# 28Pins_Schematic.net
KiCad netlist of a schematic drawn in Altium Designer
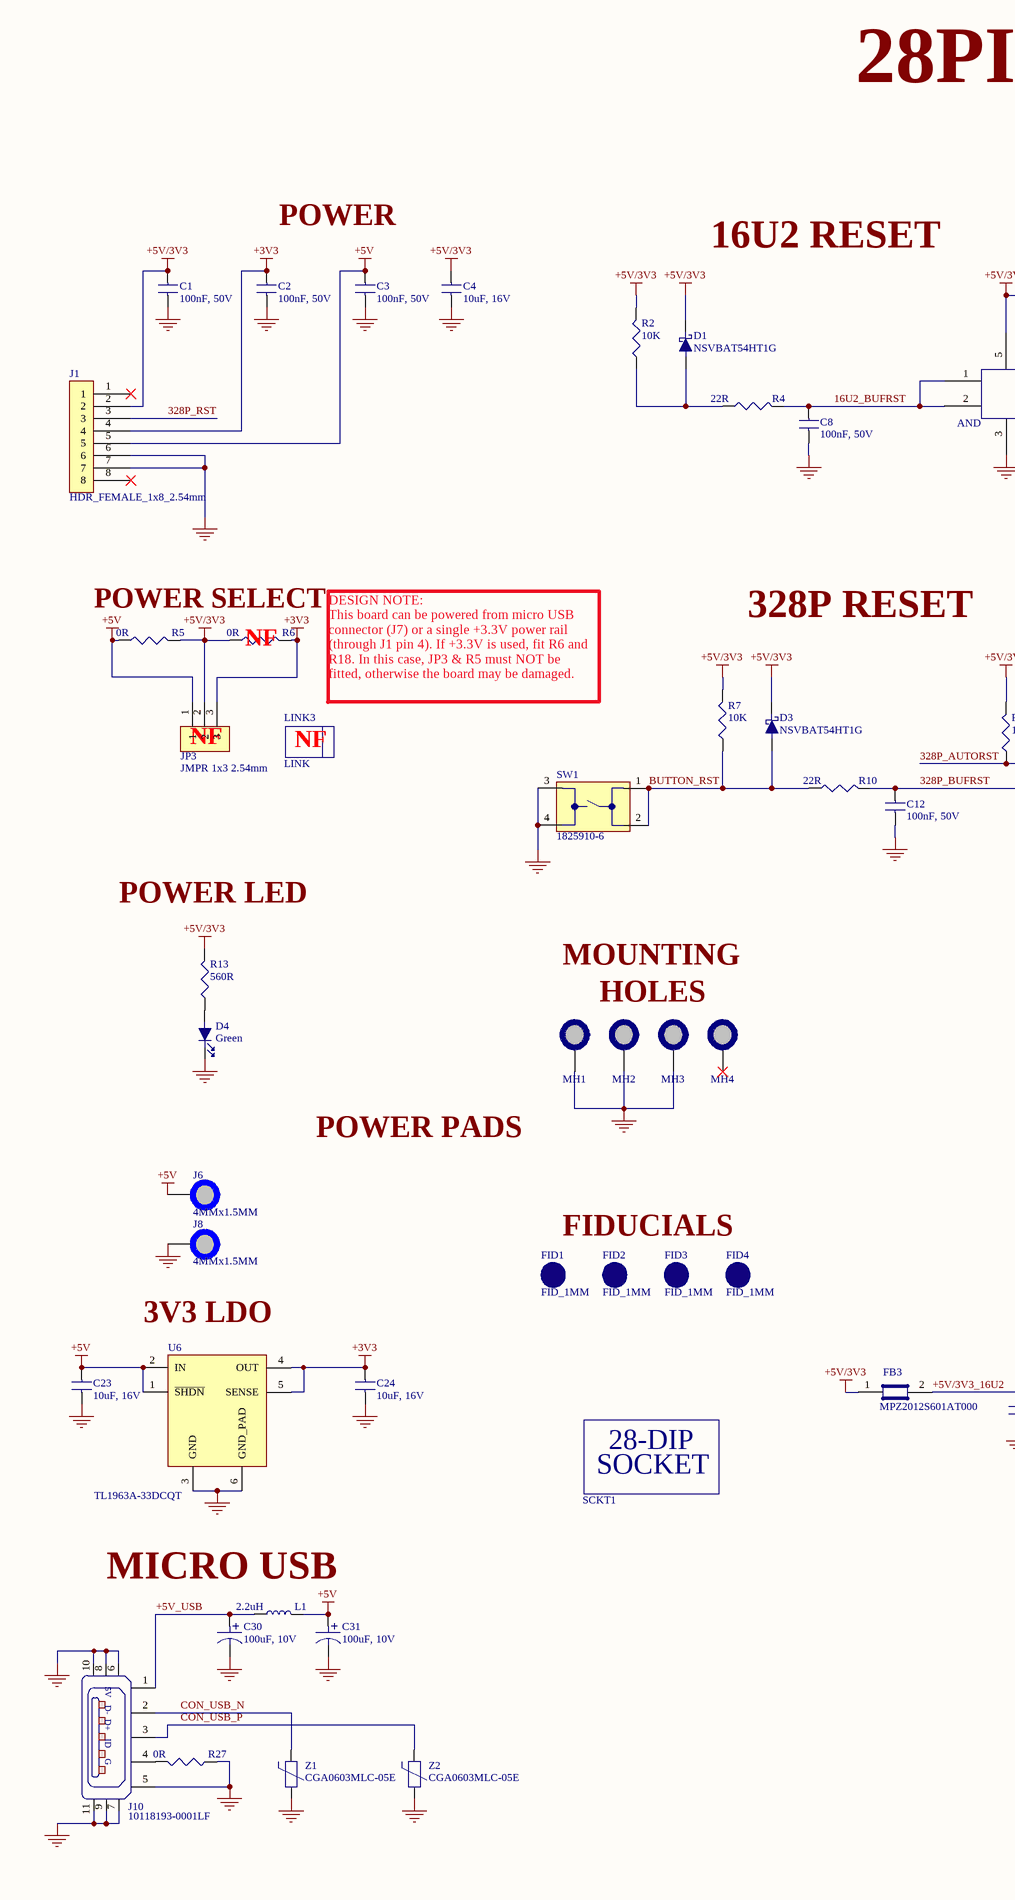
[diagram p0: 28Pins Schematic.SchDoc, left]
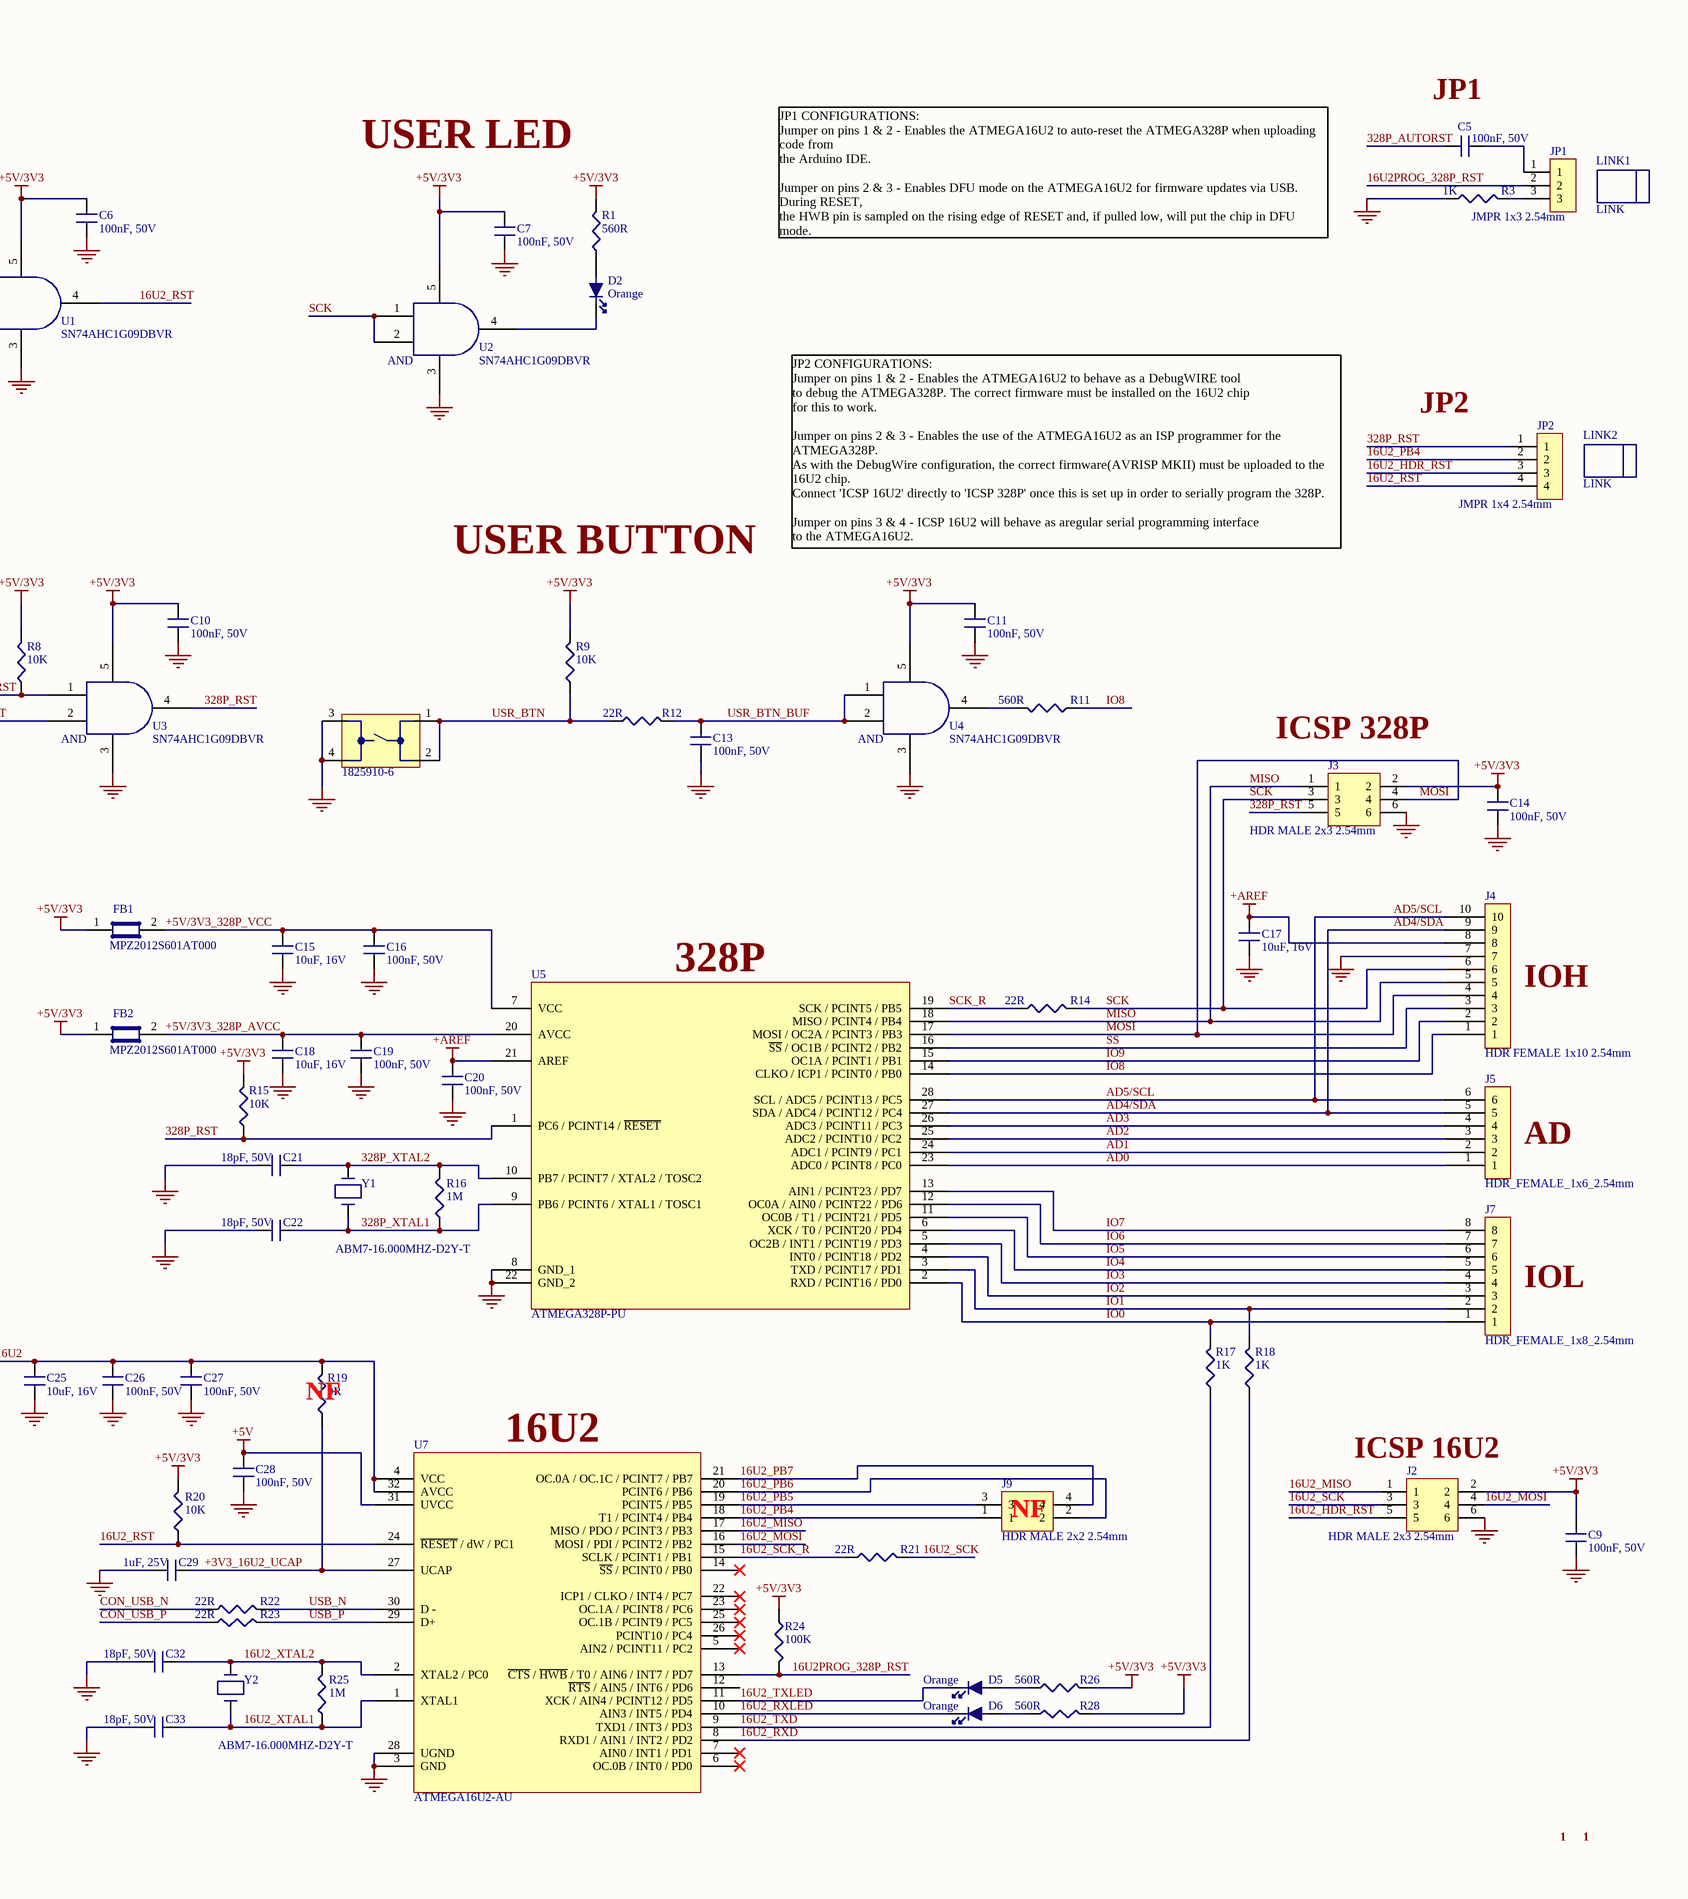
[diagram p1: 28Pins Schematic.SchDoc, right]

(export (version "E")
  (design (tool "Eeschema 10.0.6"))
  (components
    (comp (ref "C1")
      (value "100nF, 50V")
      (footprint "C0805")
      (fields
        (field (name "MANUFACTURER") "TDK")
        (field (name "MANUFACTURER PART NUMBER") "C2012X7R1H104K085AA")
        (field (name "PCN PART NUMBER") "MLCC Part Number Change 30/Nov/2012")
      )
      (libsource (lib "Arduino_V01") (part "C2012X7R1H104K085AA"))
    )
    (comp (ref "C2")
      (value "100nF, 50V")
      (footprint "C0805")
      (fields
        (field (name "MANUFACTURER") "TDK")
        (field (name "MANUFACTURER PART NUMBER") "C2012X7R1H104K085AA")
        (field (name "PCN PART NUMBER") "MLCC Part Number Change 30/Nov/2012")
      )
      (libsource (lib "Arduino_V01") (part "C2012X7R1H104K085AA"))
    )
    (comp (ref "C3")
      (value "100nF, 50V")
      (footprint "C0805")
      (fields
        (field (name "MANUFACTURER") "TDK")
        (field (name "MANUFACTURER PART NUMBER") "C2012X7R1H104K085AA")
        (field (name "PCN PART NUMBER") "MLCC Part Number Change 30/Nov/2012")
      )
      (libsource (lib "Arduino_V01") (part "C2012X7R1H104K085AA"))
    )
    (comp (ref "C4")
      (value "10uF, 16V")
      (footprint "C0805_1.25MM_HEIGHT")
      (description "Automotive Grade MLCC, 0805, X5R, 16V, 10 F, 20%, 1.25mm")
      (fields
        (field (name "MANUFACTURER") "TDK")
        (field (name "MANUFACTURER PART NUMBER") "CGA4J1X5R1C106M125AC")
      )
      (libsource (lib "Arduino_V01") (part "CGA4J1X5R1C106M125AC"))
    )
    (comp (ref "C5")
      (value "100nF, 50V")
      (footprint "C0805")
      (fields
        (field (name "MANUFACTURER") "TDK")
        (field (name "MANUFACTURER PART NUMBER") "C2012X7R1H104K085AA")
        (field (name "PCN PART NUMBER") "MLCC Part Number Change 30/Nov/2012")
      )
      (libsource (lib "Arduino_V01") (part "C2012X7R1H104K085AA"))
    )
    (comp (ref "C6")
      (value "100nF, 50V")
      (footprint "C0805")
      (fields
        (field (name "MANUFACTURER") "TDK")
        (field (name "MANUFACTURER PART NUMBER") "C2012X7R1H104K085AA")
        (field (name "PCN PART NUMBER") "MLCC Part Number Change 30/Nov/2012")
      )
      (libsource (lib "Arduino_V01") (part "C2012X7R1H104K085AA"))
    )
    (comp (ref "C7")
      (value "100nF, 50V")
      (footprint "C0805")
      (fields
        (field (name "MANUFACTURER") "TDK")
        (field (name "MANUFACTURER PART NUMBER") "C2012X7R1H104K085AA")
        (field (name "PCN PART NUMBER") "MLCC Part Number Change 30/Nov/2012")
      )
      (libsource (lib "Arduino_V01") (part "C2012X7R1H104K085AA"))
    )
    (comp (ref "C8")
      (value "100nF, 50V")
      (footprint "C0805")
      (fields
        (field (name "MANUFACTURER") "TDK")
        (field (name "MANUFACTURER PART NUMBER") "C2012X7R1H104K085AA")
        (field (name "PCN PART NUMBER") "MLCC Part Number Change 30/Nov/2012")
      )
      (libsource (lib "Arduino_V01") (part "C2012X7R1H104K085AA"))
    )
    (comp (ref "C9")
      (value "100nF, 50V")
      (footprint "C0805")
      (fields
        (field (name "MANUFACTURER") "TDK")
        (field (name "MANUFACTURER PART NUMBER") "C2012X7R1H104K085AA")
        (field (name "PCN PART NUMBER") "MLCC Part Number Change 30/Nov/2012")
      )
      (libsource (lib "Arduino_V01") (part "C2012X7R1H104K085AA"))
    )
    (comp (ref "C10")
      (value "100nF, 50V")
      (footprint "C0805")
      (fields
        (field (name "MANUFACTURER") "TDK")
        (field (name "MANUFACTURER PART NUMBER") "C2012X7R1H104K085AA")
        (field (name "PCN PART NUMBER") "MLCC Part Number Change 30/Nov/2012")
      )
      (libsource (lib "Arduino_V01") (part "C2012X7R1H104K085AA"))
    )
    (comp (ref "C11")
      (value "100nF, 50V")
      (footprint "C0805")
      (fields
        (field (name "MANUFACTURER") "TDK")
        (field (name "MANUFACTURER PART NUMBER") "C2012X7R1H104K085AA")
        (field (name "PCN PART NUMBER") "MLCC Part Number Change 30/Nov/2012")
      )
      (libsource (lib "Arduino_V01") (part "C2012X7R1H104K085AA"))
    )
    (comp (ref "C12")
      (value "100nF, 50V")
      (footprint "C0805")
      (fields
        (field (name "MANUFACTURER") "TDK")
        (field (name "MANUFACTURER PART NUMBER") "C2012X7R1H104K085AA")
        (field (name "PCN PART NUMBER") "MLCC Part Number Change 30/Nov/2012")
      )
      (libsource (lib "Arduino_V01") (part "C2012X7R1H104K085AA"))
    )
    (comp (ref "C13")
      (value "100nF, 50V")
      (footprint "C0805")
      (fields
        (field (name "MANUFACTURER") "TDK")
        (field (name "MANUFACTURER PART NUMBER") "C2012X7R1H104K085AA")
        (field (name "PCN PART NUMBER") "MLCC Part Number Change 30/Nov/2012")
      )
      (libsource (lib "Arduino_V01") (part "C2012X7R1H104K085AA"))
    )
    (comp (ref "C14")
      (value "100nF, 50V")
      (footprint "C0805")
      (fields
        (field (name "MANUFACTURER") "TDK")
        (field (name "MANUFACTURER PART NUMBER") "C2012X7R1H104K085AA")
        (field (name "PCN PART NUMBER") "MLCC Part Number Change 30/Nov/2012")
      )
      (libsource (lib "Arduino_V01") (part "C2012X7R1H104K085AA"))
    )
    (comp (ref "C15")
      (value "10uF, 16V")
      (footprint "C0805_1.25MM_HEIGHT")
      (description "Automotive Grade MLCC, 0805, X5R, 16V, 10 F, 20%, 1.25mm")
      (fields
        (field (name "MANUFACTURER") "TDK")
        (field (name "MANUFACTURER PART NUMBER") "CGA4J1X5R1C106M125AC")
      )
      (libsource (lib "Arduino_V01") (part "CGA4J1X5R1C106M125AC"))
    )
    (comp (ref "C16")
      (value "100nF, 50V")
      (footprint "C0805")
      (fields
        (field (name "MANUFACTURER") "TDK")
        (field (name "MANUFACTURER PART NUMBER") "C2012X7R1H104K085AA")
        (field (name "PCN PART NUMBER") "MLCC Part Number Change 30/Nov/2012")
      )
      (libsource (lib "Arduino_V01") (part "C2012X7R1H104K085AA"))
    )
    (comp (ref "C17")
      (value "10uF, 16V")
      (footprint "C0805_1.25MM_HEIGHT")
      (description "Automotive Grade MLCC, 0805, X5R, 16V, 10 F, 20%, 1.25mm")
      (fields
        (field (name "MANUFACTURER") "TDK")
        (field (name "MANUFACTURER PART NUMBER") "CGA4J1X5R1C106M125AC")
      )
      (libsource (lib "Arduino_V01") (part "CGA4J1X5R1C106M125AC"))
    )
    (comp (ref "C18")
      (value "10uF, 16V")
      (footprint "C0805_1.25MM_HEIGHT")
      (description "Automotive Grade MLCC, 0805, X5R, 16V, 10 F, 20%, 1.25mm")
      (fields
        (field (name "MANUFACTURER") "TDK")
        (field (name "MANUFACTURER PART NUMBER") "CGA4J1X5R1C106M125AC")
      )
      (libsource (lib "Arduino_V01") (part "CGA4J1X5R1C106M125AC"))
    )
    (comp (ref "C19")
      (value "100nF, 50V")
      (footprint "C0805")
      (fields
        (field (name "MANUFACTURER") "TDK")
        (field (name "MANUFACTURER PART NUMBER") "C2012X7R1H104K085AA")
        (field (name "PCN PART NUMBER") "MLCC Part Number Change 30/Nov/2012")
      )
      (libsource (lib "Arduino_V01") (part "C2012X7R1H104K085AA"))
    )
    (comp (ref "C20")
      (value "100nF, 50V")
      (footprint "C0805")
      (fields
        (field (name "MANUFACTURER") "TDK")
        (field (name "MANUFACTURER PART NUMBER") "C2012X7R1H104K085AA")
        (field (name "PCN PART NUMBER") "MLCC Part Number Change 30/Nov/2012")
      )
      (libsource (lib "Arduino_V01") (part "C2012X7R1H104K085AA"))
    )
    (comp (ref "C21")
      (value "18pF, 50V")
      (footprint "C0805")
      (description "CAP CER 18PF 50V C0G/NP0 0805")
      (fields
        (field (name "MANUFACTURER") "KEMET")
        (field (name "MANUFACTURER PART NUMBER") "C0805C180J5GACTU")
      )
      (libsource (lib "Arduino_V01") (part "C0805C180J5GACTU"))
    )
    (comp (ref "C22")
      (value "18pF, 50V")
      (footprint "C0805")
      (description "CAP CER 18PF 50V C0G/NP0 0805")
      (fields
        (field (name "MANUFACTURER") "KEMET")
        (field (name "MANUFACTURER PART NUMBER") "C0805C180J5GACTU")
      )
      (libsource (lib "Arduino_V01") (part "C0805C180J5GACTU"))
    )
    (comp (ref "C23")
      (value "10uF, 16V")
      (footprint "C0805_1.25MM_HEIGHT")
      (description "Automotive Grade MLCC, 0805, X5R, 16V, 10 F, 20%, 1.25mm")
      (fields
        (field (name "MANUFACTURER") "TDK")
        (field (name "MANUFACTURER PART NUMBER") "CGA4J1X5R1C106M125AC")
      )
      (libsource (lib "Arduino_V01") (part "CGA4J1X5R1C106M125AC"))
    )
    (comp (ref "C24")
      (value "10uF, 16V")
      (footprint "C0805_1.25MM_HEIGHT")
      (description "Automotive Grade MLCC, 0805, X5R, 16V, 10 F, 20%, 1.25mm")
      (fields
        (field (name "MANUFACTURER") "TDK")
        (field (name "MANUFACTURER PART NUMBER") "CGA4J1X5R1C106M125AC")
      )
      (libsource (lib "Arduino_V01") (part "CGA4J1X5R1C106M125AC"))
    )
    (comp (ref "C25")
      (value "10uF, 16V")
      (footprint "C0805_1.25MM_HEIGHT")
      (description "Automotive Grade MLCC, 0805, X5R, 16V, 10 F, 20%, 1.25mm")
      (fields
        (field (name "MANUFACTURER") "TDK")
        (field (name "MANUFACTURER PART NUMBER") "CGA4J1X5R1C106M125AC")
      )
      (libsource (lib "Arduino_V01") (part "CGA4J1X5R1C106M125AC"))
    )
    (comp (ref "C26")
      (value "100nF, 50V")
      (footprint "C0805")
      (fields
        (field (name "MANUFACTURER") "TDK")
        (field (name "MANUFACTURER PART NUMBER") "C2012X7R1H104K085AA")
        (field (name "PCN PART NUMBER") "MLCC Part Number Change 30/Nov/2012")
      )
      (libsource (lib "Arduino_V01") (part "C2012X7R1H104K085AA"))
    )
    (comp (ref "C27")
      (value "100nF, 50V")
      (footprint "C0805")
      (fields
        (field (name "MANUFACTURER") "TDK")
        (field (name "MANUFACTURER PART NUMBER") "C2012X7R1H104K085AA")
        (field (name "PCN PART NUMBER") "MLCC Part Number Change 30/Nov/2012")
      )
      (libsource (lib "Arduino_V01") (part "C2012X7R1H104K085AA"))
    )
    (comp (ref "C28")
      (value "100nF, 50V")
      (footprint "C0805")
      (fields
        (field (name "MANUFACTURER") "TDK")
        (field (name "MANUFACTURER PART NUMBER") "C2012X7R1H104K085AA")
        (field (name "PCN PART NUMBER") "MLCC Part Number Change 30/Nov/2012")
      )
      (libsource (lib "Arduino_V01") (part "C2012X7R1H104K085AA"))
    )
    (comp (ref "C29")
      (value "1uF, 25V")
      (footprint "C0805")
      (description "CAP CER 1UF 25V X7R 0805")
      (fields
        (field (name "MANUFACTURER") "TDK")
        (field (name "MANUFACTURER PART NUMBER") "CGA4J3X7R1E105K125AB")
      )
      (libsource (lib "Arduino_V01") (part "CGA4J3X7R1E105K125AB"))
    )
    (comp (ref "C30")
      (value "100uF, 10V")
      (footprint "C_ALU_C_SIZE")
      (description "Cap Aluminum 100uF 10V 20% (5 X 5.4mm) SMD 50mA 1000 hr 85°C T/R")
      (fields
        (field (name "MANUFACTURER") "Panasonic")
        (field (name "MANUFACTURER PART NUMBER") "EEE-1AA101WR")
      )
      (libsource (lib "Arduino_V01") (part "EEE-1AA101WR"))
    )
    (comp (ref "C31")
      (value "100uF, 10V")
      (footprint "C_ALU_C_SIZE")
      (description "Cap Aluminum 100uF 10V 20% (5 X 5.4mm) SMD 50mA 1000 hr 85°C T/R")
      (fields
        (field (name "MANUFACTURER") "Panasonic")
        (field (name "MANUFACTURER PART NUMBER") "EEE-1AA101WR")
      )
      (libsource (lib "Arduino_V01") (part "EEE-1AA101WR"))
    )
    (comp (ref "C32")
      (value "18pF, 50V")
      (footprint "C0805")
      (description "CAP CER 18PF 50V C0G/NP0 0805")
      (fields
        (field (name "MANUFACTURER") "KEMET")
        (field (name "MANUFACTURER PART NUMBER") "C0805C180J5GACTU")
      )
      (libsource (lib "Arduino_V01") (part "C0805C180J5GACTU"))
    )
    (comp (ref "C33")
      (value "18pF, 50V")
      (footprint "C0805")
      (description "CAP CER 18PF 50V C0G/NP0 0805")
      (fields
        (field (name "MANUFACTURER") "KEMET")
        (field (name "MANUFACTURER PART NUMBER") "C0805C180J5GACTU")
      )
      (libsource (lib "Arduino_V01") (part "C0805C180J5GACTU"))
    )
    (comp (ref "D1")
      (value "NSVBAT54HT1G")
      (footprint "D_ BAT54HT1G")
      (description "Schottky Diodes & Rectifiers SS SCHOTTKY DIODE")
      (fields (field (name "MANUFACTURER") "ON Semiconductor"))
      (libsource (lib "Arduino_V01") (part "NSVBAT54HT1G"))
    )
    (comp (ref "D2")
      (value "Orange")
      (footprint "LED_0603_Orange")
      (description "OSRAM - LO L29K-H2K1-24-Z - SMARTLED 0603 ORANGE")
      (fields
        (field (name "MANUFACTURER") "Osram Opto")
        (field (name "MANUFACTURER PART NUMBER") "LOL29K-H2K1-24-Z")
      )
      (libsource (lib "Arduino_V01") (part "LOL29K-H2K1-24-Z"))
    )
    (comp (ref "D3")
      (value "NSVBAT54HT1G")
      (footprint "D_ BAT54HT1G")
      (description "Schottky Diodes & Rectifiers SS SCHOTTKY DIODE")
      (fields (field (name "MANUFACTURER") "ON Semiconductor"))
      (libsource (lib "Arduino_V01") (part "NSVBAT54HT1G"))
    )
    (comp (ref "D4")
      (value "Green")
      (footprint "LED_0603_GREEN")
      (description "LED Uni-Color Green 572nm Automotive 2-Pin Chip 0603(1608Metric) T/R")
      (fields
        (field (name "MANUFACTURER") "Osram Opto")
        (field (name "MANUFACTURER PART NUMBER") "LGL29K-F2J1-24-Z")
      )
      (libsource (lib "Arduino_V01") (part "LGL29K-F2J1-24-Z"))
    )
    (comp (ref "D5")
      (value "Orange")
      (footprint "LED_0603_Orange")
      (description "OSRAM - LO L29K-H2K1-24-Z - SMARTLED 0603 ORANGE")
      (fields
        (field (name "MANUFACTURER") "Osram Opto")
        (field (name "MANUFACTURER PART NUMBER") "LOL29K-H2K1-24-Z")
      )
      (libsource (lib "Arduino_V01") (part "LOL29K-H2K1-24-Z"))
    )
    (comp (ref "D6")
      (value "Orange")
      (footprint "LED_0603_Orange")
      (description "OSRAM - LO L29K-H2K1-24-Z - SMARTLED 0603 ORANGE")
      (fields
        (field (name "MANUFACTURER") "Osram Opto")
        (field (name "MANUFACTURER PART NUMBER") "LOL29K-H2K1-24-Z")
      )
      (libsource (lib "Arduino_V01") (part "LOL29K-H2K1-24-Z"))
    )
    (comp (ref "FB1")
      (value "MPZ2012S601AT000")
      (footprint "C0805")
      (description "FERRITE BEAD 600 OHM 0805 1LN")
      (fields (field (name "MANUFACTURER") "TDK") (field (name "PCN PART NUMBER") "MMZ,MPS Series Oct/2014"))
      (libsource (lib "Arduino_V01") (part "MPZ2012S601AT000"))
    )
    (comp (ref "FB2")
      (value "MPZ2012S601AT000")
      (footprint "C0805")
      (description "FERRITE BEAD 600 OHM 0805 1LN")
      (fields (field (name "MANUFACTURER") "TDK") (field (name "PCN PART NUMBER") "MMZ,MPS Series Oct/2014"))
      (libsource (lib "Arduino_V01") (part "MPZ2012S601AT000"))
    )
    (comp (ref "FB3")
      (value "MPZ2012S601AT000")
      (footprint "C0805")
      (description "FERRITE BEAD 600 OHM 0805 1LN")
      (fields (field (name "MANUFACTURER") "TDK") (field (name "PCN PART NUMBER") "MMZ,MPS Series Oct/2014"))
      (libsource (lib "Arduino_V01") (part "MPZ2012S601AT000"))
    )
    (comp (ref "FID1")
      (value "FID_1MM")
      (footprint "FID_40X120D")
      (description "Fiducial 40mil diameter, 120mil mask")
      (libsource (lib "Arduino_V01") (part "FID_1MM"))
    )
    (comp (ref "FID2")
      (value "FID_1MM")
      (footprint "FID_40X120D")
      (description "Fiducial 40mil diameter, 120mil mask")
      (libsource (lib "Arduino_V01") (part "FID_1MM"))
    )
    (comp (ref "FID3")
      (value "FID_1MM")
      (footprint "FID_40X120D")
      (description "Fiducial 40mil diameter, 120mil mask")
      (libsource (lib "Arduino_V01") (part "FID_1MM"))
    )
    (comp (ref "FID4")
      (value "FID_1MM")
      (footprint "FID_40X120D")
      (description "Fiducial 40mil diameter, 120mil mask")
      (libsource (lib "Arduino_V01") (part "FID_1MM"))
    )
    (comp (ref "J1")
      (value "HDR_FEMALE_1x8_2.54mm")
      (footprint "HDR_FEMALE_1x8_2.54mm")
      (description "2.54mm (0.1\") Pitch SIL Vertical PC Tail Socket Assembly, selective gold + tin, 8 contacts")
      (fields (field (name "MANUFACTURER") "Harwin") (field (name "MANUFACTURER PART NUMBER") "M20-7820842"))
      (libsource (lib "Arduino_V01") (part "M20-7820842"))
    )
    (comp (ref "J2")
      (value "HDR MALE 2x3 2.54mm")
      (footprint "HDR_MALE_2x3_2.54MM")
      (description "CONN HEADER VERT 6POS 2.54MM")
      (fields
        (field (name "MANUFACTURER") "Amphenol FCI")
        (field (name "MANUFACTURER PART NUMBER") "67997-206HLF")
      )
      (libsource (lib "Arduino_V01") (part "67997-206HLF"))
    )
    (comp (ref "J3")
      (value "HDR MALE 2x3 2.54mm")
      (footprint "HDR_MALE_2x3_2.54MM")
      (description "CONN HEADER VERT 6POS 2.54MM")
      (fields
        (field (name "MANUFACTURER") "Amphenol FCI")
        (field (name "MANUFACTURER PART NUMBER") "67997-206HLF")
      )
      (libsource (lib "Arduino_V01") (part "67997-206HLF"))
    )
    (comp (ref "J4")
      (value "HDR FEMALE 1x10 2.54mm")
      (fields (field (name "MANUFACTURER") "Harwin") (field (name "MANUFACTURER PART NUMBER") "M20-7821046"))
      (libsource (lib "Arduino_V01") (part "M20-7821046"))
    )
    (comp (ref "J5")
      (value "HDR_FEMALE_1x6_2.54mm")
      (footprint "HDR_FEMALE_1x6_2.54mm")
      (description "Conn Socket Strip SKT 6 POS 2.54mm Solder ST Thru-Hole Tube")
      (fields (field (name "MANUFACTURER") "Harwin") (field (name "MANUFACTURER PART NUMBER") "M20-7820642"))
      (libsource (lib "Arduino_V01") (part "M20-7820642"))
    )
    (comp (ref "J6")
      (value "4MMx1.5MM")
      (footprint "PAD_WITH_HOLE_4MMx1.5MM")
      (description "PAD_WITH_HOLE_4MMx1.5MM")
      (libsource (lib "Arduino_V01") (part "PAD_WITH_HOLE_4MMx1.5MM"))
    )
    (comp (ref "J7")
      (value "HDR_FEMALE_1x8_2.54mm")
      (footprint "HDR_FEMALE_1x8_2.54mm")
      (description "2.54mm (0.1\") Pitch SIL Vertical PC Tail Socket Assembly, selective gold + tin, 8 contacts")
      (fields (field (name "MANUFACTURER") "Harwin") (field (name "MANUFACTURER PART NUMBER") "M20-7820842"))
      (libsource (lib "") (part "M20-7820842_1"))
    )
    (comp (ref "J8")
      (value "4MMx1.5MM")
      (footprint "PAD_WITH_HOLE_4MMx1.5MM")
      (description "PAD_WITH_HOLE_4MMx1.5MM")
      (libsource (lib "Arduino_V01") (part "PAD_WITH_HOLE_4MMx1.5MM"))
    )
    (comp (ref "J9")
      (value "HDR MALE 2x2 2.54mm")
      (footprint "HDR_MALE_2x2_2.54MM")
      (description "CONN HEADER VERT 4POS 2.54MM")
      (fields
        (field (name "MANUFACTURER") "Amphenol FCI")
        (field (name "MANUFACTURER PART NUMBER") "68602-204HLF")
      )
      (libsource (lib "Arduino_V01") (part "68602-204HLF"))
    )
    (comp (ref "J10")
      (value "10118193-0001LF")
      (footprint "10118193-0001LF")
      (description "CONN USB MICRO B RECPT SMT R/A")
      (fields (field (name "MANUFACTURER") "Amphenol FCI"))
      (libsource (lib "Arduino_V01") (part "10118193-0001LF"))
    )
    (comp (ref "JP1")
      (value "JMPR 1x3 2.54mm")
      (footprint "JMPR_1x3_2.54MM")
      (description "CONN HEADER VERT 3POS 2.54MM")
      (fields
        (field (name "MANUFACTURER") "Amphenol FCI")
        (field (name "MANUFACTURER PART NUMBER") "68000-203HLF")
      )
      (libsource (lib "") (part "68000-203HLF_1"))
    )
    (comp (ref "JP2")
      (value "JMPR 1x4 2.54mm")
      (footprint "JMPR_1x4_2.54mm")
      (description "CONN HEADER VERT 4POS 2.54MM")
      (fields
        (field (name "MANUFACTURER") "Amphenol FCI")
        (field (name "MANUFACTURER PART NUMBER") "68001-204HLF")
      )
      (libsource (lib "Arduino_V01") (part "68001-204HLF"))
    )
    (comp (ref "JP3")
      (value "JMPR 1x3 2.54mm")
      (footprint "JMPR_1x3_2.54MM")
      (description "CONN HEADER VERT 3POS 2.54MM")
      (fields
        (field (name "MANUFACTURER") "Amphenol FCI")
        (field (name "MANUFACTURER PART NUMBER") "68000-203HLF")
      )
      (libsource (lib "Arduino_V01") (part "68000-203HLF"))
    )
    (comp (ref "L1")
      (value "2.2uH")
      (footprint "C1210_IND")
      (description "FIXED IND 2.2UH 2A 80 MOHM SMD")
      (fields
        (field (name "MANUFACTURER") "KEMET")
        (field (name "MANUFACTURER PART NUMBER") "L1210R2R2MDWIT")
      )
      (libsource (lib "Arduino_V01") (part "L1210R2R2MDWIT"))
    )
    (comp (ref "LINK1")
      (value "LINK")
      (description "CONN JUMPER SHORTING .100\" GOLD")
      (fields
        (field (name "MANUFACTURER") "Sullins")
        (field (name "MANUFACTURER PART NUMBER") "QPC02SXGN-RC")
      )
      (libsource (lib "Arduino_V01") (part "QPC02SXGN-RC"))
    )
    (comp (ref "LINK2")
      (value "LINK")
      (description "CONN JUMPER SHORTING .100\" GOLD")
      (fields
        (field (name "MANUFACTURER") "Sullins")
        (field (name "MANUFACTURER PART NUMBER") "QPC02SXGN-RC")
      )
      (libsource (lib "Arduino_V01") (part "QPC02SXGN-RC"))
    )
    (comp (ref "LINK3")
      (value "LINK")
      (description "CONN JUMPER SHORTING .100\" GOLD")
      (fields
        (field (name "MANUFACTURER") "Sullins")
        (field (name "MANUFACTURER PART NUMBER") "QPC02SXGN-RC")
      )
      (libsource (lib "Arduino_V01") (part "QPC02SXGN-RC"))
    )
    (comp (ref "MH1")
      (value "MH_7.4MMC_3.2MMD")
      (footprint "MH_7.4MMH_3.2MMD")
      (description "Mounting hole 7.4mm diameter, 3.2mm drill")
      (libsource (lib "Arduino_V01") (part "MH_7.4MMC_3.2MMD"))
    )
    (comp (ref "MH2")
      (value "MH_7.4MMC_3.2MMD")
      (footprint "MH_7.4MMH_3.2MMD")
      (description "Mounting hole 7.4mm diameter, 3.2mm drill")
      (libsource (lib "Arduino_V01") (part "MH_7.4MMC_3.2MMD"))
    )
    (comp (ref "MH3")
      (value "MH_7.4MMC_3.2MMD")
      (footprint "MH_7.4MMH_3.2MMD")
      (description "Mounting hole 7.4mm diameter, 3.2mm drill")
      (libsource (lib "Arduino_V01") (part "MH_7.4MMC_3.2MMD"))
    )
    (comp (ref "MH4")
      (value "MH_7.4MMNC_3.2MMD")
      (footprint "MH_7.4MMNC_3.2MMD")
      (description "Mounting hole 7.4mm diameter (non copper) 3.2mm drill NPTH")
      (libsource (lib "Arduino_V01") (part "MH_7.4MMNC_3"))
    )
    (comp (ref "R1")
      (value "560R")
      (footprint "R0805")
      (description "Surface Mount Thick Film Resistor, RC Series, 560 ohm, 125 mW, - 1%, 150 V, 0805 [2012 Metric]")
      (fields
        (field (name "MANUFACTURER") "Yageo")
        (field (name "MANUFACTURER PART NUMBER") "RC0805FR-07560RL")
      )
      (libsource (lib "Arduino_V01") (part "RC0805FR-07560RL"))
    )
    (comp (ref "R2")
      (value "10K")
      (description "RES SMD 10K OHM 1% 1/8W 0805")
      (fields
        (field (name "MANUFACTURER") "Yageo")
        (field (name "MANUFACTURER PART NUMBER") "RC0805FR-0710KL")
      )
      (libsource (lib "Arduino_V01") (part "RC0805FR-0710KL"))
    )
    (comp (ref "R3")
      (value "1K")
      (footprint "R0805")
      (fields
        (field (name "MANUFACTURER") "Yageo")
        (field (name "MANUFACTURER PART NUMBER") "RC0805FR-071KL")
        (field (name "TOLERANCE") "1 %")
      )
      (libsource (lib "Arduino_V01") (part "RC0805FR-071KL"))
    )
    (comp (ref "R4")
      (value "22R")
      (footprint "R0805")
      (description "RES SMD 22 OHM 1% 1/8W 0805")
      (fields
        (field (name "MANUFACTURER") "Yageo")
        (field (name "MANUFACTURER PART NUMBER") "AC0805FR-0722RL")
      )
      (libsource (lib "Arduino_V01") (part "AC0805FR-0722RL"))
    )
    (comp (ref "R5")
      (value "0R")
      (footprint "R0805")
      (description "Surface Mount Thick Film Resistor, RC Series, 125 mW, - 5%, 150 V, 0805 [2012 Metric]")
      (fields
        (field (name "MANUFACTURER") "Yageo")
        (field (name "MANUFACTURER PART NUMBER") "RC0805JR-070RL")
      )
      (libsource (lib "Arduino_V01") (part "RC0805JR-070RL"))
    )
    (comp (ref "R6")
      (value "0R")
      (footprint "R0805")
      (description "Surface Mount Thick Film Resistor, RC Series, 125 mW, - 5%, 150 V, 0805 [2012 Metric]")
      (fields
        (field (name "MANUFACTURER") "Yageo")
        (field (name "MANUFACTURER PART NUMBER") "RC0805JR-070RL")
      )
      (libsource (lib "Arduino_V01") (part "RC0805JR-070RL"))
    )
    (comp (ref "R7")
      (value "10K")
      (description "RES SMD 10K OHM 1% 1/8W 0805")
      (fields
        (field (name "MANUFACTURER") "Yageo")
        (field (name "MANUFACTURER PART NUMBER") "RC0805FR-0710KL")
      )
      (libsource (lib "Arduino_V01") (part "RC0805FR-0710KL"))
    )
    (comp (ref "R8")
      (value "10K")
      (description "RES SMD 10K OHM 1% 1/8W 0805")
      (fields
        (field (name "MANUFACTURER") "Yageo")
        (field (name "MANUFACTURER PART NUMBER") "RC0805FR-0710KL")
      )
      (libsource (lib "Arduino_V01") (part "RC0805FR-0710KL"))
    )
    (comp (ref "R9")
      (value "10K")
      (description "RES SMD 10K OHM 1% 1/8W 0805")
      (fields
        (field (name "MANUFACTURER") "Yageo")
        (field (name "MANUFACTURER PART NUMBER") "RC0805FR-0710KL")
      )
      (libsource (lib "Arduino_V01") (part "RC0805FR-0710KL"))
    )
    (comp (ref "R10")
      (value "22R")
      (footprint "R0805")
      (description "RES SMD 22 OHM 1% 1/8W 0805")
      (fields
        (field (name "MANUFACTURER") "Yageo")
        (field (name "MANUFACTURER PART NUMBER") "AC0805FR-0722RL")
      )
      (libsource (lib "Arduino_V01") (part "AC0805FR-0722RL"))
    )
    (comp (ref "R11")
      (value "560R")
      (footprint "R0805")
      (description "Surface Mount Thick Film Resistor, RC Series, 560 ohm, 125 mW, - 1%, 150 V, 0805 [2012 Metric]")
      (fields
        (field (name "MANUFACTURER") "Yageo")
        (field (name "MANUFACTURER PART NUMBER") "RC0805FR-07560RL")
      )
      (libsource (lib "Arduino_V01") (part "RC0805FR-07560RL"))
    )
    (comp (ref "R12")
      (value "22R")
      (footprint "R0805")
      (description "RES SMD 22 OHM 1% 1/8W 0805")
      (fields
        (field (name "MANUFACTURER") "Yageo")
        (field (name "MANUFACTURER PART NUMBER") "AC0805FR-0722RL")
      )
      (libsource (lib "Arduino_V01") (part "AC0805FR-0722RL"))
    )
    (comp (ref "R13")
      (value "560R")
      (footprint "R0805")
      (description "Surface Mount Thick Film Resistor, RC Series, 560 ohm, 125 mW, - 1%, 150 V, 0805 [2012 Metric]")
      (fields
        (field (name "MANUFACTURER") "Yageo")
        (field (name "MANUFACTURER PART NUMBER") "RC0805FR-07560RL")
      )
      (libsource (lib "Arduino_V01") (part "RC0805FR-07560RL"))
    )
    (comp (ref "R14")
      (value "22R")
      (footprint "R0805")
      (description "RES SMD 22 OHM 1% 1/8W 0805")
      (fields
        (field (name "MANUFACTURER") "Yageo")
        (field (name "MANUFACTURER PART NUMBER") "AC0805FR-0722RL")
      )
      (libsource (lib "Arduino_V01") (part "AC0805FR-0722RL"))
    )
    (comp (ref "R15")
      (value "10K")
      (description "RES SMD 10K OHM 1% 1/8W 0805")
      (fields
        (field (name "MANUFACTURER") "Yageo")
        (field (name "MANUFACTURER PART NUMBER") "RC0805FR-0710KL")
      )
      (libsource (lib "Arduino_V01") (part "RC0805FR-0710KL"))
    )
    (comp (ref "R16")
      (value "1M")
      (footprint "R0805")
      (description "RES SMD 1M OHM 1% 1/8W 0805")
      (fields
        (field (name "MANUFACTURER") "Yageo")
        (field (name "MANUFACTURER PART NUMBER") "RC0805FR-071ML")
      )
      (libsource (lib "Arduino_V01") (part "RC0805FR-071ML"))
    )
    (comp (ref "R17")
      (value "1K")
      (footprint "R0805")
      (fields
        (field (name "MANUFACTURER") "Yageo")
        (field (name "MANUFACTURER PART NUMBER") "RC0805FR-071KL")
        (field (name "TOLERANCE") "1 %")
      )
      (libsource (lib "Arduino_V01") (part "RC0805FR-071KL"))
    )
    (comp (ref "R18")
      (value "1K")
      (footprint "R0805")
      (fields
        (field (name "MANUFACTURER") "Yageo")
        (field (name "MANUFACTURER PART NUMBER") "RC0805FR-071KL")
        (field (name "TOLERANCE") "1 %")
      )
      (libsource (lib "Arduino_V01") (part "RC0805FR-071KL"))
    )
    (comp (ref "R19")
      (value "0R")
      (footprint "R0805")
      (description "Surface Mount Thick Film Resistor, RC Series, 125 mW, - 5%, 150 V, 0805 [2012 Metric]")
      (fields
        (field (name "MANUFACTURER") "Yageo")
        (field (name "MANUFACTURER PART NUMBER") "RC0805JR-070RL")
      )
      (libsource (lib "Arduino_V01") (part "RC0805JR-070RL"))
    )
    (comp (ref "R20")
      (value "10K")
      (description "RES SMD 10K OHM 1% 1/8W 0805")
      (fields
        (field (name "MANUFACTURER") "Yageo")
        (field (name "MANUFACTURER PART NUMBER") "RC0805FR-0710KL")
      )
      (libsource (lib "Arduino_V01") (part "RC0805FR-0710KL"))
    )
    (comp (ref "R21")
      (value "22R")
      (footprint "R0805")
      (description "RES SMD 22 OHM 1% 1/8W 0805")
      (fields
        (field (name "MANUFACTURER") "Yageo")
        (field (name "MANUFACTURER PART NUMBER") "AC0805FR-0722RL")
      )
      (libsource (lib "Arduino_V01") (part "AC0805FR-0722RL"))
    )
    (comp (ref "R22")
      (value "22R")
      (footprint "R0805")
      (description "RES SMD 22 OHM 1% 1/8W 0805")
      (fields
        (field (name "MANUFACTURER") "Yageo")
        (field (name "MANUFACTURER PART NUMBER") "AC0805FR-0722RL")
      )
      (libsource (lib "Arduino_V01") (part "AC0805FR-0722RL"))
    )
    (comp (ref "R23")
      (value "22R")
      (footprint "R0805")
      (description "RES SMD 22 OHM 1% 1/8W 0805")
      (fields
        (field (name "MANUFACTURER") "Yageo")
        (field (name "MANUFACTURER PART NUMBER") "AC0805FR-0722RL")
      )
      (libsource (lib "Arduino_V01") (part "AC0805FR-0722RL"))
    )
    (comp (ref "R24")
      (value "100K")
      (footprint "R0805")
      (description "YAGEO         RC0805FR-07100KL            RES, THICK FILM, 100K, 1%, 0.125W, 0805, REEL")
      (fields
        (field (name "MANUFACTURER") "Yageo")
        (field (name "MANUFACTURER PART NUMBER") "RC0805FR-07100KL")
      )
      (libsource (lib "Arduino_V01") (part "RC0805FR-07100KL"))
    )
    (comp (ref "R25")
      (value "1M")
      (footprint "R0805")
      (description "RES SMD 1M OHM 1% 1/8W 0805")
      (fields
        (field (name "MANUFACTURER") "Yageo")
        (field (name "MANUFACTURER PART NUMBER") "RC0805FR-071ML")
      )
      (libsource (lib "Arduino_V01") (part "RC0805FR-071ML"))
    )
    (comp (ref "R26")
      (value "560R")
      (footprint "R0805")
      (description "Surface Mount Thick Film Resistor, RC Series, 560 ohm, 125 mW, - 1%, 150 V, 0805 [2012 Metric]")
      (fields
        (field (name "MANUFACTURER") "Yageo")
        (field (name "MANUFACTURER PART NUMBER") "RC0805FR-07560RL")
      )
      (libsource (lib "Arduino_V01") (part "RC0805FR-07560RL"))
    )
    (comp (ref "R27")
      (value "0R")
      (footprint "R0805")
      (description "Surface Mount Thick Film Resistor, RC Series, 125 mW, - 5%, 150 V, 0805 [2012 Metric]")
      (fields
        (field (name "MANUFACTURER") "Yageo")
        (field (name "MANUFACTURER PART NUMBER") "RC0805JR-070RL")
      )
      (libsource (lib "Arduino_V01") (part "RC0805JR-070RL"))
    )
    (comp (ref "R28")
      (value "560R")
      (footprint "R0805")
      (description "Surface Mount Thick Film Resistor, RC Series, 560 ohm, 125 mW, - 1%, 150 V, 0805 [2012 Metric]")
      (fields
        (field (name "MANUFACTURER") "Yageo")
        (field (name "MANUFACTURER PART NUMBER") "RC0805FR-07560RL")
      )
      (libsource (lib "Arduino_V01") (part "RC0805FR-07560RL"))
    )
    (comp (ref "SCKT1")
      (value "28-DIP Socket")
      (footprint "28-DIP_SCKT_2.54MM")
      (description "CONN IC DIP SOCKET 28POS TIN")
      (fields (field (name "MANUFACTURER") "3M") (field (name "MANUFACTURER PART NUMBER") "4828-3004-CP"))
      (libsource (lib "Arduino_V01") (part "4828-3004-CP"))
    )
    (comp (ref "SW1")
      (value "1825910-6")
      (footprint "1825910-6")
      (fields (field (name "MANUFACTURER") "ALCOSWITCH - TE CONNECTIVITY"))
      (libsource (lib "Arduino_V01") (part "1825910-6"))
    )
    (comp (ref "SW2")
      (value "1825910-6")
      (footprint "1825910-6")
      (fields (field (name "MANUFACTURER") "ALCOSWITCH - TE CONNECTIVITY"))
      (libsource (lib "Arduino_V01") (part "1825910-6"))
    )
    (comp (ref "U1")
      (value "SN74AHC1G09DBVR")
      (footprint "DBV_SOT23_5")
      (description "TEXAS INSTRUMENTS - SN74AHC1G09DBVR - AND Gate, 74AHC1G09, 2 Input, 2 V to 5.5 V, SOT-23-5")
      (fields (field (name "MANUFACTURER") "Texas Instruments"))
      (libsource (lib "Arduino_V01") (part "SN74AHC1G09DBVR"))
    )
    (comp (ref "U2")
      (value "SN74AHC1G09DBVR")
      (footprint "DBV_SOT23_5")
      (description "TEXAS INSTRUMENTS - SN74AHC1G09DBVR - AND Gate, 74AHC1G09, 2 Input, 2 V to 5.5 V, SOT-23-5")
      (fields (field (name "MANUFACTURER") "Texas Instruments"))
      (libsource (lib "Arduino_V01") (part "SN74AHC1G09DBVR"))
    )
    (comp (ref "U3")
      (value "SN74AHC1G09DBVR")
      (footprint "DBV_SOT23_5")
      (description "TEXAS INSTRUMENTS - SN74AHC1G09DBVR - AND Gate, 74AHC1G09, 2 Input, 2 V to 5.5 V, SOT-23-5")
      (fields (field (name "MANUFACTURER") "Texas Instruments"))
      (libsource (lib "Arduino_V01") (part "SN74AHC1G09DBVR"))
    )
    (comp (ref "U4")
      (value "SN74AHC1G09DBVR")
      (footprint "DBV_SOT23_5")
      (description "TEXAS INSTRUMENTS - SN74AHC1G09DBVR - AND Gate, 74AHC1G09, 2 Input, 2 V to 5.5 V, SOT-23-5")
      (fields (field (name "MANUFACTURER") "Texas Instruments"))
      (libsource (lib "Arduino_V01") (part "SN74AHC1G09DBVR"))
    )
    (comp (ref "U5")
      (value "ATMEGA328P-PU")
      (footprint "28_DIP_7.62mm")
      (description "ATMEGA328P-PU; 8 bit Microcontroller AVR 20MHz 1; 32kb Flash; 2kb RAM; I2C SPI 2")
      (fields (field (name "MANUFACTURER") "Microchip / Atmel"))
      (libsource (lib "Arduino_V01") (part "ATMEGA328P-PU"))
    )
    (comp (ref "U6")
      (value "TL1963A-33DCQT")
      (footprint "TL1963A-33DCQT")
      (description "Single Output LDO, 1.5A, 3.3V Fast Trans")
      (fields (field (name "MANUFACTURER") "Texas Instruments"))
      (libsource (lib "Arduino_V01") (part "TL1963A-33DCQT"))
    )
    (comp (ref "U7")
      (value "ATMEGA16U2-AU")
      (footprint "TQFP32")
      (description "MICROCHIP - ATMEGA16U2-AU - MCU, 8BIT, MEGAAVR, 16MHZ, TQFP-32")
      (fields (field (name "MANUFACTURER") "Microchip / Atmel"))
      (libsource (lib "Arduino_V01") (part "ATMEGA16U2-AU"))
    )
    (comp (ref "Y1")
      (value "ABM7-16.000MHZ-D2Y-T")
      (footprint "ABM7_16MHZ_XTAL_SMD")
      (description "CRYSTAL 16.0000MHZ 18PF SMD")
      (fields (field (name "MANUFACTURER") "Abracon"))
      (libsource (lib "Arduino_V01") (part "ABM7-16.000MHZ-D2Y-T"))
    )
    (comp (ref "Y2")
      (value "ABM7-16.000MHZ-D2Y-T")
      (footprint "ABM7_16MHZ_XTAL_SMD")
      (description "CRYSTAL 16.0000MHZ 18PF SMD")
      (fields (field (name "MANUFACTURER") "Abracon"))
      (libsource (lib "Arduino_V01") (part "ABM7-16.000MHZ-D2Y-T"))
    )
    (comp (ref "Z1")
      (value "CGA0603MLC-05E")
      (footprint "R0603")
      (description "ESD Suppressor TVS Bi-Dir 5V Automotive 2-Pin Case 0603(1608Metric) T/R")
      (fields (field (name "MANUFACTURER") "Bourns"))
      (libsource (lib "Arduino_V01") (part "CGA0603MLC-05E"))
    )
    (comp (ref "Z2")
      (value "CGA0603MLC-05E")
      (footprint "R0603")
      (description "ESD Suppressor TVS Bi-Dir 5V Automotive 2-Pin Case 0603(1608Metric) T/R")
      (fields (field (name "MANUFACTURER") "Bourns"))
      (libsource (lib "Arduino_V01") (part "CGA0603MLC-05E"))
    )
  )
  (nets
    (net (code "1") (name "+3V3") (class "Default")
      (node (ref "C2") (pin "2") (pinfunction "2_2") (pintype "passive"))
      (node (ref "C24") (pin "2") (pinfunction "2_2") (pintype "passive"))
      (node (ref "J1") (pin "4") (pinfunction "4_4") (pintype "passive"))
      (node (ref "JP3") (pin "3") (pinfunction "3_3") (pintype "passive"))
      (node (ref "R6") (pin "2") (pinfunction "2_2") (pintype "passive"))
      (node (ref "U6") (pin "4") (pinfunction "OUT_4") (pintype "passive"))
      (node (ref "U6") (pin "5") (pinfunction "SENSE_5") (pintype "passive"))
    )
    (net (code "2") (name "+5V") (class "Default")
      (node (ref "C23") (pin "2") (pinfunction "2_2") (pintype "passive"))
      (node (ref "C28") (pin "2") (pinfunction "2_2") (pintype "passive"))
      (node (ref "C3") (pin "2") (pinfunction "2_2") (pintype "passive"))
      (node (ref "C31") (pin "1") (pinfunction "1_1") (pintype "passive"))
      (node (ref "J1") (pin "5") (pinfunction "5_5") (pintype "passive"))
      (node (ref "J6") (pin "1") (pinfunction "1_1") (pintype "passive"))
      (node (ref "JP3") (pin "1") (pinfunction "1_1") (pintype "passive"))
      (node (ref "L1") (pin "2") (pinfunction "2_2") (pintype "passive"))
      (node (ref "R5") (pin "1") (pinfunction "1_1") (pintype "passive"))
      (node (ref "U6") (pin "1") (pinfunction "~{SHDN}_1") (pintype "passive"))
      (node (ref "U6") (pin "2") (pinfunction "IN_2") (pintype "passive"))
      (node (ref "U7") (pin "31") (pinfunction "UVCC_31") (pintype "passive"))
    )
    (net (code "3") (name "+5V{slash}3V3") (class "Default")
      (node (ref "C1") (pin "2") (pinfunction "2_2") (pintype "passive"))
      (node (ref "C10") (pin "2") (pinfunction "2_2") (pintype "passive"))
      (node (ref "C11") (pin "2") (pinfunction "2_2") (pintype "passive"))
      (node (ref "C14") (pin "2") (pinfunction "2_2") (pintype "passive"))
      (node (ref "C4") (pin "2") (pinfunction "2_2") (pintype "passive"))
      (node (ref "C6") (pin "2") (pinfunction "2_2") (pintype "passive"))
      (node (ref "C7") (pin "2") (pinfunction "2_2") (pintype "passive"))
      (node (ref "C9") (pin "2") (pinfunction "2_2") (pintype "passive"))
      (node (ref "D1") (pin "2") (pinfunction "K_2") (pintype "passive"))
      (node (ref "D3") (pin "2") (pinfunction "K_2") (pintype "passive"))
      (node (ref "FB1") (pin "1") (pinfunction "1_1") (pintype "passive"))
      (node (ref "FB2") (pin "1") (pinfunction "1_1") (pintype "passive"))
      (node (ref "FB3") (pin "1") (pinfunction "1_1") (pintype "passive"))
      (node (ref "J1") (pin "2") (pinfunction "2_2") (pintype "passive"))
      (node (ref "J2") (pin "2") (pinfunction "2_2") (pintype "passive"))
      (node (ref "J3") (pin "2") (pinfunction "2_2") (pintype "passive"))
      (node (ref "JP3") (pin "2") (pinfunction "2_2") (pintype "passive"))
      (node (ref "R1") (pin "2") (pinfunction "2_2") (pintype "passive"))
      (node (ref "R13") (pin "2") (pinfunction "2_2") (pintype "passive"))
      (node (ref "R15") (pin "2") (pinfunction "2_2") (pintype "passive"))
      (node (ref "R2") (pin "2") (pinfunction "2_2") (pintype "passive"))
      (node (ref "R20") (pin "2") (pinfunction "2_2") (pintype "passive"))
      (node (ref "R24") (pin "1") (pinfunction "1_1") (pintype "passive"))
      (node (ref "R26") (pin "2") (pinfunction "2_2") (pintype "passive"))
      (node (ref "R28") (pin "2") (pinfunction "2_2") (pintype "passive"))
      (node (ref "R5") (pin "2") (pinfunction "2_2") (pintype "passive"))
      (node (ref "R6") (pin "1") (pinfunction "1_1") (pintype "passive"))
      (node (ref "R7") (pin "2") (pinfunction "2_2") (pintype "passive"))
      (node (ref "R8") (pin "2") (pinfunction "2_2") (pintype "passive"))
      (node (ref "R9") (pin "2") (pinfunction "2_2") (pintype "passive"))
      (node (ref "U1") (pin "5") (pinfunction "5_5") (pintype "passive"))
      (node (ref "U2") (pin "5") (pinfunction "5_5") (pintype "passive"))
      (node (ref "U3") (pin "5") (pinfunction "5_5") (pintype "passive"))
      (node (ref "U4") (pin "5") (pinfunction "5_5") (pintype "passive"))
    )
    (net (code "4") (name "+AREF") (class "Default")
      (node (ref "C17") (pin "2") (pinfunction "2_2") (pintype "passive"))
      (node (ref "C20") (pin "2") (pinfunction "2_2") (pintype "passive"))
      (node (ref "J4") (pin "8") (pinfunction "8_8") (pintype "passive"))
      (node (ref "U5") (pin "21") (pinfunction "AREF_21") (pintype "passive"))
    )
    (net (code "5") (name "/+3V3_16U2_UCAP") (class "Default")
      (node (ref "C29") (pin "1") (pinfunction "1_1") (pintype "passive"))
      (node (ref "R19") (pin "1") (pinfunction "1_1") (pintype "passive"))
      (node (ref "U7") (pin "27") (pinfunction "UCAP_27") (pintype "passive"))
    )
    (net (code "6") (name "/+5V_USB") (class "Default")
      (node (ref "C30") (pin "1") (pinfunction "1_1") (pintype "passive"))
      (node (ref "J10") (pin "1") (pinfunction "1_1") (pintype "passive"))
      (node (ref "L1") (pin "1") (pinfunction "1_1") (pintype "passive"))
    )
    (net (code "7") (name "/+5V{slash}3V3_16U2") (class "Default")
      (node (ref "C25") (pin "2") (pinfunction "2_2") (pintype "passive"))
      (node (ref "C26") (pin "2") (pinfunction "2_2") (pintype "passive"))
      (node (ref "C27") (pin "2") (pinfunction "2_2") (pintype "passive"))
      (node (ref "FB3") (pin "2") (pinfunction "2_2") (pintype "passive"))
      (node (ref "R19") (pin "2") (pinfunction "2_2") (pintype "passive"))
      (node (ref "U7") (pin "32") (pinfunction "AVCC_32") (pintype "passive"))
      (node (ref "U7") (pin "4") (pinfunction "VCC_4") (pintype "passive"))
    )
    (net (code "8") (name "/+5V{slash}3V3_328P_AVCC") (class "Default")
      (node (ref "C18") (pin "2") (pinfunction "2_2") (pintype "passive"))
      (node (ref "C19") (pin "2") (pinfunction "2_2") (pintype "passive"))
      (node (ref "FB2") (pin "2") (pinfunction "2_2") (pintype "passive"))
      (node (ref "U5") (pin "20") (pinfunction "AVCC_20") (pintype "passive"))
    )
    (net (code "9") (name "/+5V{slash}3V3_328P_VCC") (class "Default")
      (node (ref "C15") (pin "2") (pinfunction "2_2") (pintype "passive"))
      (node (ref "C16") (pin "2") (pinfunction "2_2") (pintype "passive"))
      (node (ref "FB1") (pin "2") (pinfunction "2_2") (pintype "passive"))
      (node (ref "U5") (pin "7") (pinfunction "VCC_7") (pintype "passive"))
    )
    (net (code "10") (name "/16U2PROG_328P_RST") (class "Default")
      (node (ref "JP1") (pin "2") (pinfunction "2_2") (pintype "passive"))
      (node (ref "R24") (pin "2") (pinfunction "2_2") (pintype "passive"))
      (node (ref "U7") (pin "13") (pinfunction "~{CTS}_/_~{HWB}_/_T0_/_AIN6_/_INT7_/_PD7_13") (pintype "passive"))
    )
    (net (code "11") (name "/16U2_BUFRST") (class "Default")
      (node (ref "C8") (pin "2") (pinfunction "2_2") (pintype "passive"))
      (node (ref "R4") (pin "2") (pinfunction "2_2") (pintype "passive"))
      (node (ref "U1") (pin "1") (pinfunction "1_1") (pintype "passive"))
      (node (ref "U1") (pin "2") (pinfunction "2_2") (pintype "passive"))
    )
    (net (code "12") (name "/16U2_HDR_RST") (class "Default")
      (node (ref "J2") (pin "5") (pinfunction "5_5") (pintype "passive"))
      (node (ref "JP2") (pin "3") (pinfunction "3_3") (pintype "passive"))
    )
    (net (code "13") (name "/16U2_MISO") (class "Default")
      (node (ref "J2") (pin "1") (pinfunction "1_1") (pintype "passive"))
      (node (ref "U7") (pin "17") (pinfunction "MISO_/_PDO_/_PCINT3_/_PB3_17") (pintype "passive"))
    )
    (net (code "14") (name "/16U2_MOSI") (class "Default")
      (node (ref "J2") (pin "4") (pinfunction "4_4") (pintype "passive"))
      (node (ref "U7") (pin "16") (pinfunction "MOSI_/_PDI_/_PCINT2_/_PB2_16") (pintype "passive"))
    )
    (net (code "15") (name "/16U2_PB4") (class "Default")
      (node (ref "J9") (pin "1") (pinfunction "1_1") (pintype "passive"))
      (node (ref "JP2") (pin "2") (pinfunction "2_2") (pintype "passive"))
      (node (ref "U7") (pin "18") (pinfunction "T1_/_PCINT4_/_PB4_18") (pintype "passive"))
    )
    (net (code "16") (name "/16U2_PB5") (class "Default")
      (node (ref "J9") (pin "3") (pinfunction "3_3") (pintype "passive"))
      (node (ref "U7") (pin "19") (pinfunction "PCINT5_/_PB5_19") (pintype "passive"))
    )
    (net (code "17") (name "/16U2_PB6") (class "Default")
      (node (ref "J9") (pin "2") (pinfunction "2_2") (pintype "passive"))
      (node (ref "U7") (pin "20") (pinfunction "PCINT6_/_PB6_20") (pintype "passive"))
    )
    (net (code "18") (name "/16U2_PB7") (class "Default")
      (node (ref "J9") (pin "4") (pinfunction "4_4") (pintype "passive"))
      (node (ref "U7") (pin "21") (pinfunction "OC.0A_/_OC.1C_/_PCINT7_/_PB7_21") (pintype "passive"))
    )
    (net (code "19") (name "/16U2_RST") (class "Default")
      (node (ref "JP2") (pin "4") (pinfunction "4_4") (pintype "passive"))
      (node (ref "R20") (pin "1") (pinfunction "1_1") (pintype "passive"))
      (node (ref "U1") (pin "4") (pinfunction "4_4") (pintype "passive"))
      (node (ref "U7") (pin "24") (pinfunction "~{RESET}_/_dW_/_PC1_24") (pintype "passive"))
    )
    (net (code "20") (name "/16U2_RXD") (class "Default")
      (node (ref "R18") (pin "1") (pinfunction "1_1") (pintype "passive"))
      (node (ref "U7") (pin "8") (pinfunction "RXD1_/_AIN1_/_INT2_/_PD2_8") (pintype "passive"))
    )
    (net (code "21") (name "/16U2_RXLED") (class "Default")
      (node (ref "D6") (pin "2") (pinfunction "K_2") (pintype "passive"))
      (node (ref "U7") (pin "10") (pinfunction "AIN3_/_INT5_/_PD4_10") (pintype "passive"))
    )
    (net (code "22") (name "/16U2_SCK") (class "Default")
      (node (ref "J2") (pin "3") (pinfunction "3_3") (pintype "passive"))
      (node (ref "R21") (pin "2") (pinfunction "2_2") (pintype "passive"))
    )
    (net (code "23") (name "/16U2_SCK_R") (class "Default")
      (node (ref "R21") (pin "1") (pinfunction "1_1") (pintype "passive"))
      (node (ref "U7") (pin "15") (pinfunction "SCLK_/_PCINT1_/_PB1_15") (pintype "passive"))
    )
    (net (code "24") (name "/16U2_TXD") (class "Default")
      (node (ref "R17") (pin "1") (pinfunction "1_1") (pintype "passive"))
      (node (ref "U7") (pin "9") (pinfunction "TXD1_/_INT3_/_PD3_9") (pintype "passive"))
    )
    (net (code "25") (name "/16U2_TXLED") (class "Default")
      (node (ref "D5") (pin "2") (pinfunction "K_2") (pintype "passive"))
      (node (ref "U7") (pin "11") (pinfunction "XCK_/_AIN4_/_PCINT12_/_PD5_11") (pintype "passive"))
    )
    (net (code "26") (name "/16U2_XTAL1") (class "Default")
      (node (ref "C33") (pin "2") (pinfunction "2_2") (pintype "passive"))
      (node (ref "R25") (pin "1") (pinfunction "1_1") (pintype "passive"))
      (node (ref "U7") (pin "1") (pinfunction "XTAL1_1") (pintype "passive"))
      (node (ref "Y2") (pin "1") (pinfunction "1_1") (pintype "passive"))
    )
    (net (code "27") (name "/16U2_XTAL2") (class "Default")
      (node (ref "C32") (pin "2") (pinfunction "2_2") (pintype "passive"))
      (node (ref "R25") (pin "2") (pinfunction "2_2") (pintype "passive"))
      (node (ref "U7") (pin "2") (pinfunction "XTAL2_/_PC0_2") (pintype "passive"))
      (node (ref "Y2") (pin "2") (pinfunction "2_2") (pintype "passive"))
    )
    (net (code "28") (name "/328P_AUTORST") (class "Default")
      (node (ref "C5") (pin "2") (pinfunction "2_2") (pintype "passive"))
      (node (ref "R8") (pin "1") (pinfunction "1_1") (pintype "passive"))
      (node (ref "U3") (pin "1") (pinfunction "1_1") (pintype "passive"))
    )
    (net (code "29") (name "/328P_BUFRST") (class "Default")
      (node (ref "C12") (pin "2") (pinfunction "2_2") (pintype "passive"))
      (node (ref "R10") (pin "2") (pinfunction "2_2") (pintype "passive"))
      (node (ref "U3") (pin "2") (pinfunction "2_2") (pintype "passive"))
    )
    (net (code "30") (name "/328P_RST") (class "Default")
      (node (ref "J1") (pin "3") (pinfunction "3_3") (pintype "passive"))
      (node (ref "J3") (pin "5") (pinfunction "5_5") (pintype "passive"))
      (node (ref "JP2") (pin "1") (pinfunction "1_1") (pintype "passive"))
      (node (ref "R15") (pin "1") (pinfunction "1_1") (pintype "passive"))
      (node (ref "U3") (pin "4") (pinfunction "4_4") (pintype "passive"))
      (node (ref "U5") (pin "1") (pinfunction "PC6_/_PCINT14_/_~{RESET}_1") (pintype "passive"))
    )
    (net (code "31") (name "/328P_XTAL1") (class "Default")
      (node (ref "C22") (pin "2") (pinfunction "2_2") (pintype "passive"))
      (node (ref "R16") (pin "1") (pinfunction "1_1") (pintype "passive"))
      (node (ref "U5") (pin "9") (pinfunction "PB6_/_PCINT6_/_XTAL1_/_TOSC1_9") (pintype "passive"))
      (node (ref "Y1") (pin "1") (pinfunction "1_1") (pintype "passive"))
    )
    (net (code "32") (name "/328P_XTAL2") (class "Default")
      (node (ref "C21") (pin "2") (pinfunction "2_2") (pintype "passive"))
      (node (ref "R16") (pin "2") (pinfunction "2_2") (pintype "passive"))
      (node (ref "U5") (pin "10") (pinfunction "PB7_/_PCINT7_/_XTAL2_/_TOSC2_10") (pintype "passive"))
      (node (ref "Y1") (pin "2") (pinfunction "2_2") (pintype "passive"))
    )
    (net (code "33") (name "/AD0") (class "Default")
      (node (ref "J5") (pin "1") (pinfunction "1_1") (pintype "passive"))
      (node (ref "U5") (pin "23") (pinfunction "ADC0_/_PCINT8_/_PC0_23") (pintype "passive"))
    )
    (net (code "34") (name "/AD1") (class "Default")
      (node (ref "J5") (pin "2") (pinfunction "2_2") (pintype "passive"))
      (node (ref "U5") (pin "24") (pinfunction "ADC1_/_PCINT9_/_PC1_24") (pintype "passive"))
    )
    (net (code "35") (name "/AD2") (class "Default")
      (node (ref "J5") (pin "3") (pinfunction "3_3") (pintype "passive"))
      (node (ref "U5") (pin "25") (pinfunction "ADC2_/_PCINT10_/_PC2_25") (pintype "passive"))
    )
    (net (code "36") (name "/AD3") (class "Default")
      (node (ref "J5") (pin "4") (pinfunction "4_4") (pintype "passive"))
      (node (ref "U5") (pin "26") (pinfunction "ADC3_/_PCINT11_/_PC3_26") (pintype "passive"))
    )
    (net (code "37") (name "/AD4{slash}SDA") (class "Default")
      (node (ref "J4") (pin "9") (pinfunction "9_9") (pintype "passive"))
      (node (ref "J5") (pin "5") (pinfunction "5_5") (pintype "passive"))
      (node (ref "U5") (pin "27") (pinfunction "SDA_/_ADC4_/_PCINT12_/_PC4_27") (pintype "passive"))
    )
    (net (code "38") (name "/AD5{slash}SCL") (class "Default")
      (node (ref "J4") (pin "10") (pinfunction "10_10") (pintype "passive"))
      (node (ref "J5") (pin "6") (pinfunction "6_6") (pintype "passive"))
      (node (ref "U5") (pin "28") (pinfunction "SCL_/_ADC5_/_PCINT13_/_PC5_28") (pintype "passive"))
    )
    (net (code "39") (name "/BUTTON_RST") (class "Default")
      (node (ref "D3") (pin "1") (pinfunction "A_1") (pintype "passive"))
      (node (ref "R10") (pin "1") (pinfunction "1_1") (pintype "passive"))
      (node (ref "R7") (pin "1") (pinfunction "1_1") (pintype "passive"))
      (node (ref "SW1") (pin "1") (pinfunction "1_1") (pintype "passive"))
      (node (ref "SW1") (pin "2") (pinfunction "2_2") (pintype "passive"))
    )
    (net (code "40") (name "/CON_USB_N") (class "Default")
      (node (ref "J10") (pin "2") (pinfunction "2_2") (pintype "passive"))
      (node (ref "R22") (pin "1") (pinfunction "1_1") (pintype "passive"))
      (node (ref "Z1") (pin "2") (pinfunction "2_2") (pintype "passive"))
    )
    (net (code "41") (name "/CON_USB_P") (class "Default")
      (node (ref "J10") (pin "3") (pinfunction "3_3") (pintype "passive"))
      (node (ref "R23") (pin "1") (pinfunction "1_1") (pintype "passive"))
      (node (ref "Z2") (pin "2") (pinfunction "2_2") (pintype "passive"))
    )
    (net (code "42") (name "/IO0") (class "Default")
      (node (ref "J7") (pin "1") (pinfunction "1_1") (pintype "passive"))
      (node (ref "R17") (pin "2") (pinfunction "2_2") (pintype "passive"))
      (node (ref "U5") (pin "2") (pinfunction "RXD_/_PCINT16_/_PD0_2") (pintype "passive"))
    )
    (net (code "43") (name "/IO1") (class "Default")
      (node (ref "J7") (pin "2") (pinfunction "2_2") (pintype "passive"))
      (node (ref "R18") (pin "2") (pinfunction "2_2") (pintype "passive"))
      (node (ref "U5") (pin "3") (pinfunction "TXD_/_PCINT17_/_PD1_3") (pintype "passive"))
    )
    (net (code "44") (name "/IO2") (class "Default")
      (node (ref "J7") (pin "3") (pinfunction "3_3") (pintype "passive"))
      (node (ref "U5") (pin "4") (pinfunction "INT0_/_PCINT18_/_PD2_4") (pintype "passive"))
    )
    (net (code "45") (name "/IO3") (class "Default")
      (node (ref "J7") (pin "4") (pinfunction "4_4") (pintype "passive"))
      (node (ref "U5") (pin "5") (pinfunction "OC2B_/_INT1_/_PCINT19_/_PD3_5") (pintype "passive"))
    )
    (net (code "46") (name "/IO4") (class "Default")
      (node (ref "J7") (pin "5") (pinfunction "5_5") (pintype "passive"))
      (node (ref "U5") (pin "6") (pinfunction "XCK_/_T0_/_PCINT20_/_PD4_6") (pintype "passive"))
    )
    (net (code "47") (name "/IO5") (class "Default")
      (node (ref "J7") (pin "6") (pinfunction "6_6") (pintype "passive"))
      (node (ref "U5") (pin "11") (pinfunction "OC0B_/_T1_/_PCINT21_/_PD5_11") (pintype "passive"))
    )
    (net (code "48") (name "/IO6") (class "Default")
      (node (ref "J7") (pin "7") (pinfunction "7_7") (pintype "passive"))
      (node (ref "U5") (pin "12") (pinfunction "OC0A_/_AIN0_/_PCINT22_/_PD6_12") (pintype "passive"))
    )
    (net (code "49") (name "/IO7") (class "Default")
      (node (ref "J7") (pin "8") (pinfunction "8_8") (pintype "passive"))
      (node (ref "U5") (pin "13") (pinfunction "AIN1_/_PCINT23_/_PD7_13") (pintype "passive"))
    )
    (net (code "50") (name "/IO8") (class "Default")
      (node (ref "J4") (pin "1") (pinfunction "1_1") (pintype "passive"))
      (node (ref "R11") (pin "1") (pinfunction "1_1") (pintype "passive"))
      (node (ref "U5") (pin "14") (pinfunction "CLKO_/_ICP1_/_PCINT0_/_PB0_14") (pintype "passive"))
    )
    (net (code "51") (name "/IO9") (class "Default")
      (node (ref "J4") (pin "2") (pinfunction "2_2") (pintype "passive"))
      (node (ref "U5") (pin "15") (pinfunction "OC1A_/_PCINT1_/_PB1_15") (pintype "passive"))
    )
    (net (code "52") (name "/MISO") (class "Default")
      (node (ref "J3") (pin "1") (pinfunction "1_1") (pintype "passive"))
      (node (ref "J4") (pin "5") (pinfunction "5_5") (pintype "passive"))
      (node (ref "U5") (pin "18") (pinfunction "MISO_/_PCINT4_/_PB4_18") (pintype "passive"))
    )
    (net (code "53") (name "/MOSI") (class "Default")
      (node (ref "J3") (pin "4") (pinfunction "4_4") (pintype "passive"))
      (node (ref "J4") (pin "4") (pinfunction "4_4") (pintype "passive"))
      (node (ref "U5") (pin "17") (pinfunction "MOSI_/_OC2A_/_PCINT3_/_PB3_17") (pintype "passive"))
    )
    (net (code "54") (name "/SCK") (class "Default")
      (node (ref "J3") (pin "3") (pinfunction "3_3") (pintype "passive"))
      (node (ref "J4") (pin "6") (pinfunction "6_6") (pintype "passive"))
      (node (ref "R14") (pin "2") (pinfunction "2_2") (pintype "passive"))
      (node (ref "U2") (pin "1") (pinfunction "1_1") (pintype "passive"))
      (node (ref "U2") (pin "2") (pinfunction "2_2") (pintype "passive"))
    )
    (net (code "55") (name "/SCK_R") (class "Default")
      (node (ref "R14") (pin "1") (pinfunction "1_1") (pintype "passive"))
      (node (ref "U5") (pin "19") (pinfunction "SCK_/_PCINT5_/_PB5_19") (pintype "passive"))
    )
    (net (code "56") (name "/SS") (class "Default")
      (node (ref "J4") (pin "3") (pinfunction "3_3") (pintype "passive"))
      (node (ref "U5") (pin "16") (pinfunction "~{SS}_/_OC1B_/_PCINT2_/_PB2_16") (pintype "passive"))
    )
    (net (code "57") (name "/USB_N") (class "Default")
      (node (ref "R22") (pin "2") (pinfunction "2_2") (pintype "passive"))
      (node (ref "U7") (pin "30") (pinfunction "D_-_30") (pintype "passive"))
    )
    (net (code "58") (name "/USB_P") (class "Default")
      (node (ref "R23") (pin "2") (pinfunction "2_2") (pintype "passive"))
      (node (ref "U7") (pin "29") (pinfunction "D+_29") (pintype "passive"))
    )
    (net (code "59") (name "/USR_BTN") (class "Default")
      (node (ref "R12") (pin "1") (pinfunction "1_1") (pintype "passive"))
      (node (ref "R9") (pin "1") (pinfunction "1_1") (pintype "passive"))
      (node (ref "SW2") (pin "1") (pinfunction "1_1") (pintype "passive"))
      (node (ref "SW2") (pin "2") (pinfunction "2_2") (pintype "passive"))
    )
    (net (code "60") (name "/USR_BTN_BUF") (class "Default")
      (node (ref "C13") (pin "2") (pinfunction "2_2") (pintype "passive"))
      (node (ref "R12") (pin "2") (pinfunction "2_2") (pintype "passive"))
      (node (ref "U4") (pin "1") (pinfunction "1_1") (pintype "passive"))
      (node (ref "U4") (pin "2") (pinfunction "2_2") (pintype "passive"))
    )
    (net (code "61") (name "GND") (class "Default")
      (node (ref "C1") (pin "1") (pinfunction "1_1") (pintype "passive"))
      (node (ref "C10") (pin "1") (pinfunction "1_1") (pintype "passive"))
      (node (ref "C11") (pin "1") (pinfunction "1_1") (pintype "passive"))
      (node (ref "C12") (pin "1") (pinfunction "1_1") (pintype "passive"))
      (node (ref "C13") (pin "1") (pinfunction "1_1") (pintype "passive"))
      (node (ref "C14") (pin "1") (pinfunction "1_1") (pintype "passive"))
      (node (ref "C15") (pin "1") (pinfunction "1_1") (pintype "passive"))
      (node (ref "C16") (pin "1") (pinfunction "1_1") (pintype "passive"))
      (node (ref "C17") (pin "1") (pinfunction "1_1") (pintype "passive"))
      (node (ref "C18") (pin "1") (pinfunction "1_1") (pintype "passive"))
      (node (ref "C19") (pin "1") (pinfunction "1_1") (pintype "passive"))
      (node (ref "C2") (pin "1") (pinfunction "1_1") (pintype "passive"))
      (node (ref "C20") (pin "1") (pinfunction "1_1") (pintype "passive"))
      (node (ref "C21") (pin "1") (pinfunction "1_1") (pintype "passive"))
      (node (ref "C22") (pin "1") (pinfunction "1_1") (pintype "passive"))
      (node (ref "C23") (pin "1") (pinfunction "1_1") (pintype "passive"))
      (node (ref "C24") (pin "1") (pinfunction "1_1") (pintype "passive"))
      (node (ref "C25") (pin "1") (pinfunction "1_1") (pintype "passive"))
      (node (ref "C26") (pin "1") (pinfunction "1_1") (pintype "passive"))
      (node (ref "C27") (pin "1") (pinfunction "1_1") (pintype "passive"))
      (node (ref "C28") (pin "1") (pinfunction "1_1") (pintype "passive"))
      (node (ref "C29") (pin "2") (pinfunction "2_2") (pintype "passive"))
      (node (ref "C3") (pin "1") (pinfunction "1_1") (pintype "passive"))
      (node (ref "C30") (pin "2") (pinfunction "2_2") (pintype "passive"))
      (node (ref "C31") (pin "2") (pinfunction "2_2") (pintype "passive"))
      (node (ref "C32") (pin "1") (pinfunction "1_1") (pintype "passive"))
      (node (ref "C33") (pin "1") (pinfunction "1_1") (pintype "passive"))
      (node (ref "C4") (pin "1") (pinfunction "1_1") (pintype "passive"))
      (node (ref "C6") (pin "1") (pinfunction "1_1") (pintype "passive"))
      (node (ref "C7") (pin "1") (pinfunction "1_1") (pintype "passive"))
      (node (ref "C8") (pin "1") (pinfunction "1_1") (pintype "passive"))
      (node (ref "C9") (pin "1") (pinfunction "1_1") (pintype "passive"))
      (node (ref "D4") (pin "2") (pinfunction "K_2") (pintype "passive"))
      (node (ref "J1") (pin "6") (pinfunction "6_6") (pintype "passive"))
      (node (ref "J1") (pin "7") (pinfunction "7_7") (pintype "passive"))
      (node (ref "J10") (pin "10") (pinfunction "10_10") (pintype "passive"))
      (node (ref "J10") (pin "11") (pinfunction "11_11") (pintype "passive"))
      (node (ref "J10") (pin "5") (pinfunction "5_5") (pintype "passive"))
      (node (ref "J10") (pin "6") (pinfunction "6_6") (pintype "passive"))
      (node (ref "J10") (pin "7") (pinfunction "7_7") (pintype "passive"))
      (node (ref "J10") (pin "8") (pinfunction "8_8") (pintype "passive"))
      (node (ref "J10") (pin "9") (pinfunction "9_9") (pintype "passive"))
      (node (ref "J2") (pin "6") (pinfunction "6_6") (pintype "passive"))
      (node (ref "J3") (pin "6") (pinfunction "6_6") (pintype "passive"))
      (node (ref "J4") (pin "7") (pinfunction "7_7") (pintype "passive"))
      (node (ref "J8") (pin "1") (pinfunction "1_1") (pintype "passive"))
      (node (ref "MH1") (pin "1") (pinfunction "1_1") (pintype "passive"))
      (node (ref "MH2") (pin "1") (pinfunction "1_1") (pintype "passive"))
      (node (ref "MH3") (pin "1") (pinfunction "1_1") (pintype "passive"))
      (node (ref "R27") (pin "1") (pinfunction "1_1") (pintype "passive"))
      (node (ref "R3") (pin "1") (pinfunction "1_1") (pintype "passive"))
      (node (ref "SW1") (pin "3") (pinfunction "3_3") (pintype "passive"))
      (node (ref "SW1") (pin "4") (pinfunction "4_4") (pintype "passive"))
      (node (ref "SW2") (pin "3") (pinfunction "3_3") (pintype "passive"))
      (node (ref "SW2") (pin "4") (pinfunction "4_4") (pintype "passive"))
      (node (ref "U1") (pin "3") (pinfunction "3_3") (pintype "passive"))
      (node (ref "U2") (pin "3") (pinfunction "3_3") (pintype "passive"))
      (node (ref "U3") (pin "3") (pinfunction "3_3") (pintype "passive"))
      (node (ref "U4") (pin "3") (pinfunction "3_3") (pintype "passive"))
      (node (ref "U5") (pin "22") (pinfunction "GND_2_22") (pintype "passive"))
      (node (ref "U5") (pin "8") (pinfunction "GND_1_8") (pintype "passive"))
      (node (ref "U6") (pin "3") (pinfunction "GND_3") (pintype "passive"))
      (node (ref "U6") (pin "6") (pinfunction "GND_PAD_6") (pintype "passive"))
      (node (ref "U7") (pin "28") (pinfunction "UGND_28") (pintype "passive"))
      (node (ref "U7") (pin "3") (pinfunction "GND_3") (pintype "passive"))
      (node (ref "Z1") (pin "1") (pinfunction "1_1") (pintype "passive"))
      (node (ref "Z2") (pin "1") (pinfunction "1_1") (pintype "passive"))
    )
    (net (code "62") (name "Net-(C5-Pad1)") (class "Default")
      (node (ref "C5") (pin "1") (pinfunction "1_1") (pintype "passive"))
      (node (ref "JP1") (pin "1") (pinfunction "1_1") (pintype "passive"))
    )
    (net (code "63") (name "Net-(D1-A)") (class "Default")
      (node (ref "D1") (pin "1") (pinfunction "A_1") (pintype "passive"))
      (node (ref "R2") (pin "1") (pinfunction "1_1") (pintype "passive"))
      (node (ref "R4") (pin "1") (pinfunction "1_1") (pintype "passive"))
    )
    (net (code "64") (name "Net-(D2-A)") (class "Default")
      (node (ref "D2") (pin "1") (pinfunction "A_1") (pintype "passive"))
      (node (ref "R1") (pin "1") (pinfunction "1_1") (pintype "passive"))
    )
    (net (code "65") (name "Net-(D2-K)") (class "Default")
      (node (ref "D2") (pin "2") (pinfunction "K_2") (pintype "passive"))
      (node (ref "U2") (pin "4") (pinfunction "4_4") (pintype "passive"))
    )
    (net (code "66") (name "Net-(D4-A)") (class "Default")
      (node (ref "D4") (pin "1") (pinfunction "A_1") (pintype "passive"))
      (node (ref "R13") (pin "1") (pinfunction "1_1") (pintype "passive"))
    )
    (net (code "67") (name "Net-(D5-A)") (class "Default")
      (node (ref "D5") (pin "1") (pinfunction "A_1") (pintype "passive"))
      (node (ref "R26") (pin "1") (pinfunction "1_1") (pintype "passive"))
    )
    (net (code "68") (name "Net-(D6-A)") (class "Default")
      (node (ref "D6") (pin "1") (pinfunction "A_1") (pintype "passive"))
      (node (ref "R28") (pin "1") (pinfunction "1_1") (pintype "passive"))
    )
    (net (code "69") (name "Net-(J10-Pad4)") (class "Default")
      (node (ref "J10") (pin "4") (pinfunction "4_4") (pintype "passive"))
      (node (ref "R27") (pin "2") (pinfunction "2_2") (pintype "passive"))
    )
    (net (code "70") (name "Net-(JP1-Pad3)") (class "Default")
      (node (ref "JP1") (pin "3") (pinfunction "3_3") (pintype "passive"))
      (node (ref "R3") (pin "2") (pinfunction "2_2") (pintype "passive"))
    )
    (net (code "71") (name "Net-(R11-Pad2)") (class "Default")
      (node (ref "R11") (pin "2") (pinfunction "2_2") (pintype "passive"))
      (node (ref "U4") (pin "4") (pinfunction "4_4") (pintype "passive"))
    )
    (net (code "72") (name "unconnected-(J1-Pad1)") (class "Default")
      (node (ref "J1") (pin "1") (pinfunction "1_1") (pintype "passive+no_connect"))
    )
    (net (code "73") (name "unconnected-(J1-Pad8)") (class "Default")
      (node (ref "J1") (pin "8") (pinfunction "8_8") (pintype "passive+no_connect"))
    )
    (net (code "74") (name "unconnected-(MH4-Pad1)") (class "Default")
      (node (ref "MH4") (pin "1") (pinfunction "1_1") (pintype "passive+no_connect"))
    )
    (net (code "75") (name "unconnected-(U7-AIN0_{slash}_INT1_{slash}_PD1-Pad7)") (class "Default")
      (node (ref "U7") (pin "7") (pinfunction "AIN0_/_INT1_/_PD1_7") (pintype "passive+no_connect"))
    )
    (net (code "76") (name "unconnected-(U7-AIN2_{slash}_PCINT11_{slash}_PC2-Pad5)") (class "Default")
      (node (ref "U7") (pin "5") (pinfunction "AIN2_/_PCINT11_/_PC2_5") (pintype "passive+no_connect"))
    )
    (net (code "77") (name "unconnected-(U7-ICP1_{slash}_CLKO_{slash}_INT4_{slash}_PC7-Pad22)") (class "Default")
      (node (ref "U7") (pin "22") (pinfunction "ICP1_/_CLKO_/_INT4_/_PC7_22") (pintype "passive+no_connect"))
    )
    (net (code "78") (name "unconnected-(U7-OC.0B_{slash}_INT0_{slash}_PD0-Pad6)") (class "Default")
      (node (ref "U7") (pin "6") (pinfunction "OC.0B_/_INT0_/_PD0_6") (pintype "passive+no_connect"))
    )
    (net (code "79") (name "unconnected-(U7-OC.1A_{slash}_PCINT8_{slash}_PC6-Pad23)") (class "Default")
      (node (ref "U7") (pin "23") (pinfunction "OC.1A_/_PCINT8_/_PC6_23") (pintype "passive+no_connect"))
    )
    (net (code "80") (name "unconnected-(U7-OC.1B_{slash}_PCINT9_{slash}_PC5-Pad25)") (class "Default")
      (node (ref "U7") (pin "25") (pinfunction "OC.1B_/_PCINT9_/_PC5_25") (pintype "passive+no_connect"))
    )
    (net (code "81") (name "unconnected-(U7-PCINT10_{slash}_PC4-Pad26)") (class "Default")
      (node (ref "U7") (pin "26") (pinfunction "PCINT10_/_PC4_26") (pintype "passive+no_connect"))
    )
    (net (code "82") (name "unconnected-(U7-~{RTS}_{slash}_AIN5_{slash}_INT6_{slash}_PD6-Pad12)") (class "Default")
      (node (ref "U7") (pin "12") (pinfunction "~{RTS}_/_AIN5_/_INT6_/_PD6_12") (pintype "passive"))
    )
    (net (code "83") (name "unconnected-(U7-~{SS}_{slash}_PCINT0_{slash}_PB0-Pad14)") (class "Default")
      (node (ref "U7") (pin "14") (pinfunction "~{SS}_/_PCINT0_/_PB0_14") (pintype "passive+no_connect"))
    )
  )
)
